# two_electrode_ECG.net
KiCad netlist of a schematic drawn in EAGLE
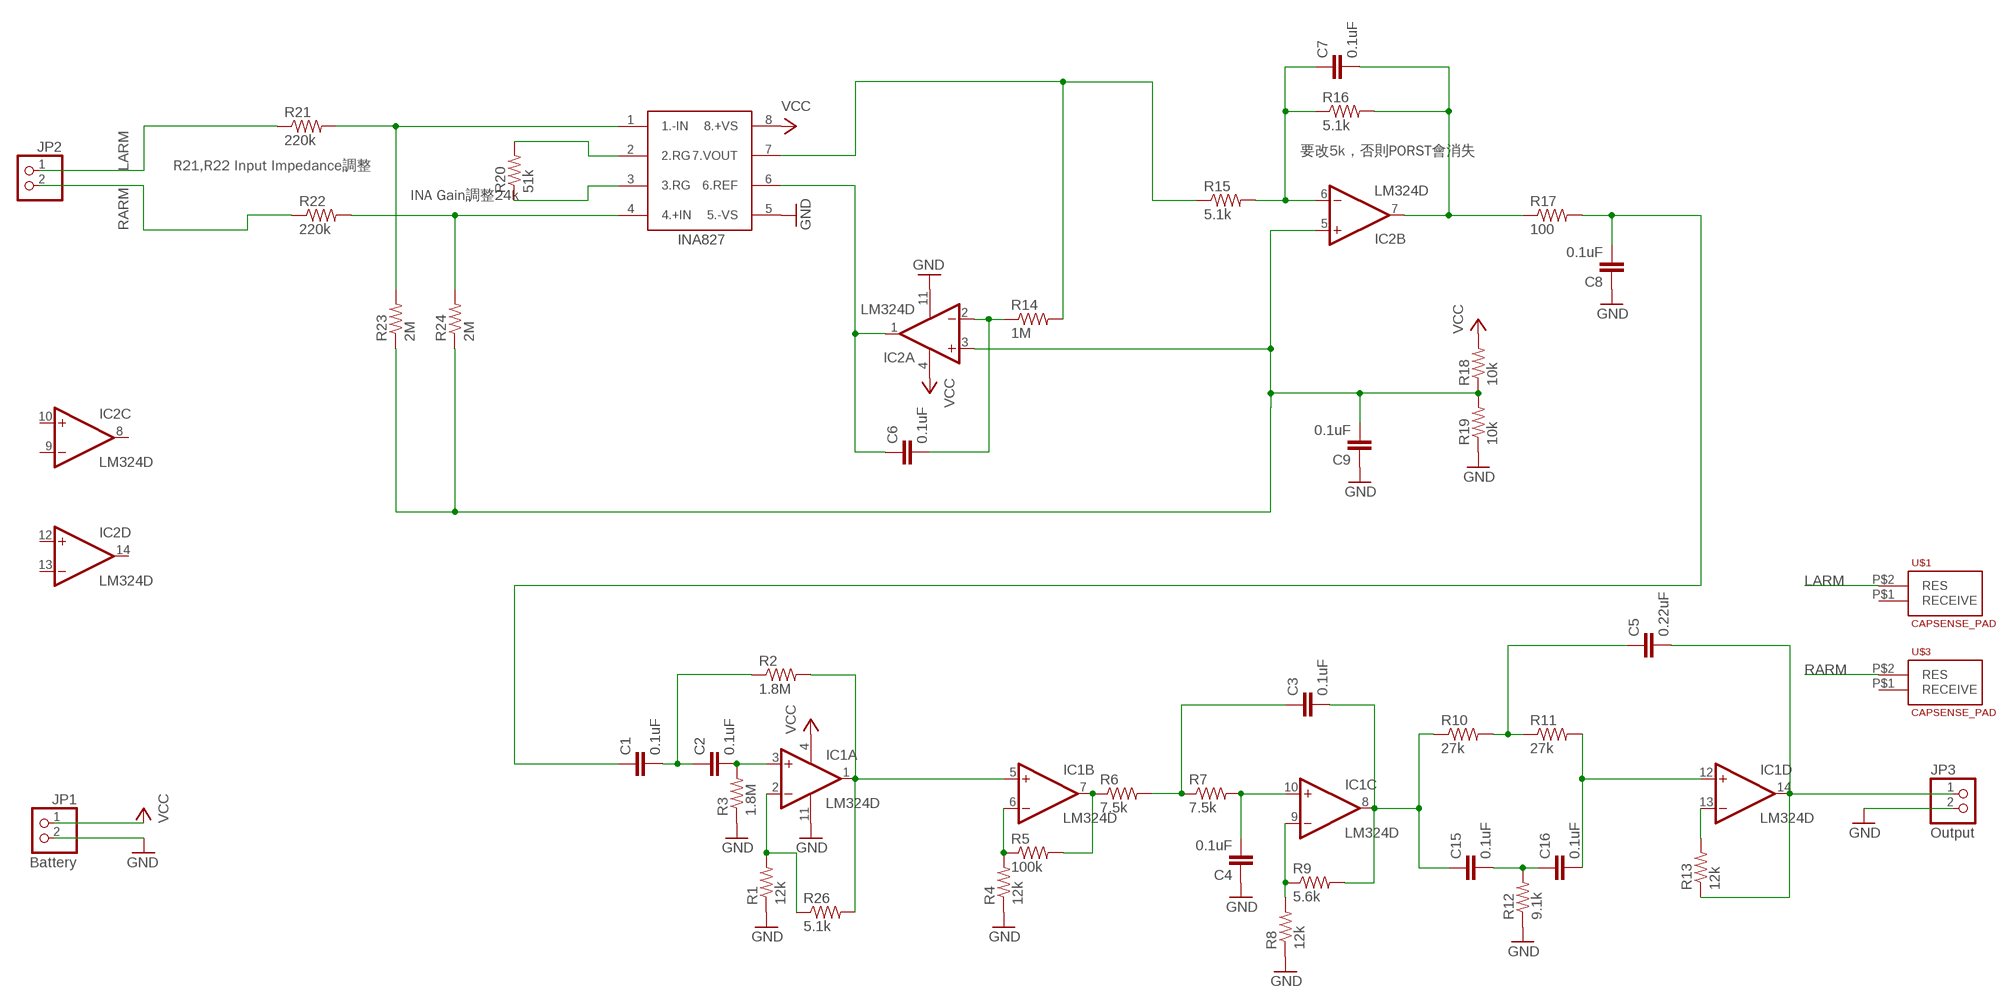
[diagram p0: schematic, sheet 1]

(export (version "E")
  (design (tool "Eeschema 10.0.6"))
  (components
    (comp (ref "C1")
      (value "0.1uF")
      (footprint "eagle-import:0603-CAP")
      (libsource (lib "eagle-import") (part "0.22UF-25V-10%(0603)"))
    )
    (comp (ref "C2")
      (value "0.1uF")
      (footprint "eagle-import:0603-CAP")
      (libsource (lib "eagle-import") (part "0.22UF-25V-10%(0603)"))
    )
    (comp (ref "C3")
      (value "0.1uF")
      (footprint "eagle-import:0603-CAP")
      (libsource (lib "eagle-import") (part "0.22UF-25V-10%(0603)"))
    )
    (comp (ref "C4")
      (value "0.1uF")
      (footprint "eagle-import:0603-CAP")
      (libsource (lib "eagle-import") (part "0.22UF-25V-10%(0603)"))
    )
    (comp (ref "C5")
      (value "0.22uF")
      (footprint "eagle-import:0603-CAP")
      (libsource (lib "eagle-import") (part "0.22UF-25V-10%(0603)"))
    )
    (comp (ref "C6")
      (value "0.1uF")
      (footprint "eagle-import:0603-CAP")
      (libsource (lib "eagle-import") (part "0.22UF-25V-10%(0603)"))
    )
    (comp (ref "C7")
      (value "0.1uF")
      (footprint "eagle-import:0603-CAP")
      (libsource (lib "eagle-import") (part "0.22UF-25V-10%(0603)"))
    )
    (comp (ref "C8")
      (value "0.1uF")
      (footprint "eagle-import:0603-CAP")
      (libsource (lib "eagle-import") (part "0.22UF-25V-10%(0603)"))
    )
    (comp (ref "C9")
      (value "0.1uF")
      (footprint "eagle-import:0603-CAP")
      (libsource (lib "eagle-import") (part "0.22UF-25V-10%(0603)"))
    )
    (comp (ref "C15")
      (value "0.1uF")
      (footprint "eagle-import:0603-CAP")
      (libsource (lib "eagle-import") (part "0.22UF-25V-10%(0603)"))
    )
    (comp (ref "C16")
      (value "0.1uF")
      (footprint "eagle-import:0603-CAP")
      (libsource (lib "eagle-import") (part "0.22UF-25V-10%(0603)"))
    )
    (comp (ref "IC1")
      (value "LM324D")
      (footprint "eagle-import:SO14")
      (libsource (lib "eagle-import") (part "LM324D"))
    )
    (comp (ref "IC2")
      (value "LM324D")
      (footprint "eagle-import:SO14")
      (libsource (lib "eagle-import") (part "LM324D"))
    )
    (comp (ref "JP1")
      (value "Battery")
      (footprint "eagle-import:1X02")
      (libsource (lib "eagle-import") (part "PINHD-1X2"))
    )
    (comp (ref "JP2")
      (value "PINHD-1X2")
      (footprint "eagle-import:1X02")
      (libsource (lib "eagle-import") (part "PINHD-1X2"))
    )
    (comp (ref "JP3")
      (value "Output")
      (footprint "eagle-import:1X02")
      (libsource (lib "eagle-import") (part "PINHD-1X2"))
    )
    (comp (ref "R1")
      (value "12k")
      (footprint "eagle-import:0603-RES")
      (libsource (lib "eagle-import") (part "1.2MOHMS-1/10W-1%(0603)"))
    )
    (comp (ref "R2")
      (value "1.8M")
      (footprint "eagle-import:0603-RES")
      (libsource (lib "eagle-import") (part "1.2MOHMS-1/10W-1%(0603)"))
    )
    (comp (ref "R3")
      (value "1.8M")
      (footprint "eagle-import:0603-RES")
      (libsource (lib "eagle-import") (part "1.2MOHMS-1/10W-1%(0603)"))
    )
    (comp (ref "R4")
      (value "12k")
      (footprint "eagle-import:0603-RES")
      (libsource (lib "eagle-import") (part "1.2MOHMS-1/10W-1%(0603)"))
    )
    (comp (ref "R5")
      (value "100k")
      (footprint "eagle-import:0603-RES")
      (libsource (lib "eagle-import") (part "1.2MOHMS-1/10W-1%(0603)"))
    )
    (comp (ref "R6")
      (value "7.5k")
      (footprint "eagle-import:0603-RES")
      (libsource (lib "eagle-import") (part "1.2MOHMS-1/10W-1%(0603)"))
    )
    (comp (ref "R7")
      (value "7.5k")
      (footprint "eagle-import:0603-RES")
      (libsource (lib "eagle-import") (part "1.2MOHMS-1/10W-1%(0603)"))
    )
    (comp (ref "R8")
      (value "12k")
      (footprint "eagle-import:0603-RES")
      (libsource (lib "eagle-import") (part "1.2MOHMS-1/10W-1%(0603)"))
    )
    (comp (ref "R9")
      (value "5.6k")
      (footprint "eagle-import:0603-RES")
      (libsource (lib "eagle-import") (part "1.2MOHMS-1/10W-1%(0603)"))
    )
    (comp (ref "R10")
      (value "27k")
      (footprint "eagle-import:0603-RES")
      (libsource (lib "eagle-import") (part "1.2MOHMS-1/10W-1%(0603)"))
    )
    (comp (ref "R11")
      (value "27k")
      (footprint "eagle-import:0603-RES")
      (libsource (lib "eagle-import") (part "1.2MOHMS-1/10W-1%(0603)"))
    )
    (comp (ref "R12")
      (value "9.1k")
      (footprint "eagle-import:0603-RES")
      (libsource (lib "eagle-import") (part "1.2MOHMS-1/10W-1%(0603)"))
    )
    (comp (ref "R13")
      (value "12k")
      (footprint "eagle-import:0603-RES")
      (libsource (lib "eagle-import") (part "1.2MOHMS-1/10W-1%(0603)"))
    )
    (comp (ref "R14")
      (value "1M")
      (footprint "eagle-import:0603-RES")
      (libsource (lib "eagle-import") (part "1.2MOHMS-1/10W-1%(0603)"))
    )
    (comp (ref "R15")
      (value "5.1k")
      (footprint "eagle-import:0603-RES")
      (libsource (lib "eagle-import") (part "1.2MOHMS-1/10W-1%(0603)"))
    )
    (comp (ref "R16")
      (value "5.1k")
      (footprint "eagle-import:0603-RES")
      (libsource (lib "eagle-import") (part "1.2MOHMS-1/10W-1%(0603)"))
    )
    (comp (ref "R17")
      (value "100")
      (footprint "eagle-import:0603-RES")
      (libsource (lib "eagle-import") (part "1.2MOHMS-1/10W-1%(0603)"))
    )
    (comp (ref "R18")
      (value "10k")
      (footprint "eagle-import:0603-RES")
      (libsource (lib "eagle-import") (part "1.2MOHMS-1/10W-1%(0603)"))
    )
    (comp (ref "R19")
      (value "10k")
      (footprint "eagle-import:0603-RES")
      (libsource (lib "eagle-import") (part "1.2MOHMS-1/10W-1%(0603)"))
    )
    (comp (ref "R20")
      (value "51k")
      (footprint "eagle-import:0603-RES")
      (libsource (lib "eagle-import") (part "1.2MOHMS-1/10W-1%(0603)"))
    )
    (comp (ref "R21")
      (value "220k")
      (footprint "eagle-import:0603-RES")
      (libsource (lib "eagle-import") (part "1.2MOHMS-1/10W-1%(0603)"))
    )
    (comp (ref "R22")
      (value "220k")
      (footprint "eagle-import:0603-RES")
      (libsource (lib "eagle-import") (part "1.2MOHMS-1/10W-1%(0603)"))
    )
    (comp (ref "R23")
      (value "2M")
      (footprint "eagle-import:0603-RES")
      (libsource (lib "eagle-import") (part "1.2MOHMS-1/10W-1%(0603)"))
    )
    (comp (ref "R24")
      (value "2M")
      (footprint "eagle-import:0603-RES")
      (libsource (lib "eagle-import") (part "1.2MOHMS-1/10W-1%(0603)"))
    )
    (comp (ref "R26")
      (value "5.1k")
      (footprint "eagle-import:0603-RES")
      (libsource (lib "eagle-import") (part "1.2MOHMS-1/10W-1%(0603)"))
    )
    (comp (ref "U$1")
      (value "CAPSENSE_PAD")
      (footprint "eagle-import:CAPSENSE_PAD")
      (libsource (lib "eagle-import") (part "CAPSENSE_PAD"))
    )
    (comp (ref "U$2")
      (value "INA827")
      (footprint "eagle-import:INA827")
      (libsource (lib "eagle-import") (part "INA827"))
    )
    (comp (ref "U$3")
      (value "CAPSENSE_PAD")
      (footprint "eagle-import:CAPSENSE_PAD")
      (libsource (lib "eagle-import") (part "CAPSENSE_PAD"))
    )
  )
  (nets
    (net (code "1") (name "/LARM") (class "Default")
      (node (ref "JP2") (pin "1") (pinfunction "1_1") (pintype "passive"))
      (node (ref "R21") (pin "1") (pinfunction "1_1") (pintype "passive"))
      (node (ref "U$1") (pin "P$2") (pinfunction "RES_P$2") (pintype "bidirectional"))
    )
    (net (code "2") (name "/RARM") (class "Default")
      (node (ref "JP2") (pin "2") (pinfunction "2_2") (pintype "passive"))
      (node (ref "R22") (pin "1") (pinfunction "1_1") (pintype "passive"))
      (node (ref "U$3") (pin "P$2") (pinfunction "RES_P$2") (pintype "bidirectional"))
    )
    (net (code "3") (name "GND") (class "Default")
      (node (ref "C4") (pin "1") (pinfunction "1_1") (pintype "passive"))
      (node (ref "C8") (pin "1") (pinfunction "1_1") (pintype "passive"))
      (node (ref "C9") (pin "1") (pinfunction "1_1") (pintype "passive"))
      (node (ref "IC1") (pin "11") (pinfunction "V-_11") (pintype "power_in"))
      (node (ref "IC2") (pin "11") (pinfunction "V-_11") (pintype "power_in"))
      (node (ref "JP1") (pin "2") (pinfunction "2_2") (pintype "passive"))
      (node (ref "JP3") (pin "2") (pinfunction "2_2") (pintype "passive"))
      (node (ref "R1") (pin "1") (pinfunction "1_1") (pintype "passive"))
      (node (ref "R12") (pin "1") (pinfunction "1_1") (pintype "passive"))
      (node (ref "R19") (pin "1") (pinfunction "1_1") (pintype "passive"))
      (node (ref "R3") (pin "1") (pinfunction "1_1") (pintype "passive"))
      (node (ref "R4") (pin "1") (pinfunction "1_1") (pintype "passive"))
      (node (ref "R8") (pin "1") (pinfunction "1_1") (pintype "passive"))
      (node (ref "U$2") (pin "5") (pinfunction "5.-VS_5") (pintype "bidirectional"))
    )
    (net (code "4") (name "Net-(C1-Pad1)") (class "Default")
      (node (ref "C1") (pin "1") (pinfunction "1_1") (pintype "passive"))
      (node (ref "C8") (pin "2") (pinfunction "2_2") (pintype "passive"))
      (node (ref "R17") (pin "2") (pinfunction "2_2") (pintype "passive"))
    )
    (net (code "5") (name "Net-(C1-Pad2)") (class "Default")
      (node (ref "C1") (pin "2") (pinfunction "2_2") (pintype "passive"))
      (node (ref "C2") (pin "1") (pinfunction "1_1") (pintype "passive"))
      (node (ref "R2") (pin "1") (pinfunction "1_1") (pintype "passive"))
    )
    (net (code "6") (name "Net-(C3-Pad1)") (class "Default")
      (node (ref "C3") (pin "1") (pinfunction "1_1") (pintype "passive"))
      (node (ref "R6") (pin "2") (pinfunction "2_2") (pintype "passive"))
      (node (ref "R7") (pin "1") (pinfunction "1_1") (pintype "passive"))
    )
    (net (code "7") (name "Net-(C5-Pad1)") (class "Default")
      (node (ref "C5") (pin "1") (pinfunction "1_1") (pintype "passive"))
      (node (ref "R10") (pin "2") (pinfunction "2_2") (pintype "passive"))
      (node (ref "R11") (pin "1") (pinfunction "1_1") (pintype "passive"))
    )
    (net (code "8") (name "Net-(C15-Pad2)") (class "Default")
      (node (ref "C15") (pin "2") (pinfunction "2_2") (pintype "passive"))
      (node (ref "C16") (pin "1") (pinfunction "1_1") (pintype "passive"))
      (node (ref "R12") (pin "2") (pinfunction "2_2") (pintype "passive"))
    )
    (net (code "9") (name "Net-(IC1A-+IN)") (class "Default")
      (node (ref "C2") (pin "2") (pinfunction "2_2") (pintype "passive"))
      (node (ref "IC1") (pin "3") (pinfunction "+IN_3") (pintype "input"))
      (node (ref "R3") (pin "2") (pinfunction "2_2") (pintype "passive"))
    )
    (net (code "10") (name "Net-(IC1A--IN)") (class "Default")
      (node (ref "IC1") (pin "2") (pinfunction "-IN_2") (pintype "input"))
      (node (ref "R1") (pin "2") (pinfunction "2_2") (pintype "passive"))
      (node (ref "R26") (pin "1") (pinfunction "1_1") (pintype "passive"))
    )
    (net (code "11") (name "Net-(IC1A-OUT)") (class "Default")
      (node (ref "IC1") (pin "1") (pinfunction "OUT_1") (pintype "output"))
      (node (ref "IC1") (pin "5") (pinfunction "+IN_5") (pintype "input"))
      (node (ref "R2") (pin "2") (pinfunction "2_2") (pintype "passive"))
      (node (ref "R26") (pin "2") (pinfunction "2_2") (pintype "passive"))
    )
    (net (code "12") (name "Net-(IC1B--IN)") (class "Default")
      (node (ref "IC1") (pin "6") (pinfunction "-IN_6") (pintype "input"))
      (node (ref "R4") (pin "2") (pinfunction "2_2") (pintype "passive"))
      (node (ref "R5") (pin "1") (pinfunction "1_1") (pintype "passive"))
    )
    (net (code "13") (name "Net-(IC1B-OUT)") (class "Default")
      (node (ref "IC1") (pin "7") (pinfunction "OUT_7") (pintype "output"))
      (node (ref "R5") (pin "2") (pinfunction "2_2") (pintype "passive"))
      (node (ref "R6") (pin "1") (pinfunction "1_1") (pintype "passive"))
    )
    (net (code "14") (name "Net-(IC1C-+IN)") (class "Default")
      (node (ref "C4") (pin "2") (pinfunction "2_2") (pintype "passive"))
      (node (ref "IC1") (pin "10") (pinfunction "+IN_10") (pintype "input"))
      (node (ref "R7") (pin "2") (pinfunction "2_2") (pintype "passive"))
    )
    (net (code "15") (name "Net-(IC1C--IN)") (class "Default")
      (node (ref "IC1") (pin "9") (pinfunction "-IN_9") (pintype "input"))
      (node (ref "R8") (pin "2") (pinfunction "2_2") (pintype "passive"))
      (node (ref "R9") (pin "1") (pinfunction "1_1") (pintype "passive"))
    )
    (net (code "16") (name "Net-(IC1C-OUT)") (class "Default")
      (node (ref "C15") (pin "1") (pinfunction "1_1") (pintype "passive"))
      (node (ref "C3") (pin "2") (pinfunction "2_2") (pintype "passive"))
      (node (ref "IC1") (pin "8") (pinfunction "OUT_8") (pintype "output"))
      (node (ref "R10") (pin "1") (pinfunction "1_1") (pintype "passive"))
      (node (ref "R9") (pin "2") (pinfunction "2_2") (pintype "passive"))
    )
    (net (code "17") (name "Net-(IC1D-+IN)") (class "Default")
      (node (ref "C16") (pin "2") (pinfunction "2_2") (pintype "passive"))
      (node (ref "IC1") (pin "12") (pinfunction "+IN_12") (pintype "input"))
      (node (ref "R11") (pin "2") (pinfunction "2_2") (pintype "passive"))
    )
    (net (code "18") (name "Net-(IC1D--IN)") (class "Default")
      (node (ref "IC1") (pin "13") (pinfunction "-IN_13") (pintype "input"))
      (node (ref "R13") (pin "2") (pinfunction "2_2") (pintype "passive"))
    )
    (net (code "19") (name "Net-(IC1D-OUT)") (class "Default")
      (node (ref "C5") (pin "2") (pinfunction "2_2") (pintype "passive"))
      (node (ref "IC1") (pin "14") (pinfunction "OUT_14") (pintype "output"))
      (node (ref "JP3") (pin "1") (pinfunction "1_1") (pintype "passive"))
      (node (ref "R13") (pin "1") (pinfunction "1_1") (pintype "passive"))
    )
    (net (code "20") (name "Net-(IC2A-+IN)") (class "Default")
      (node (ref "C9") (pin "2") (pinfunction "2_2") (pintype "passive"))
      (node (ref "IC2") (pin "3") (pinfunction "+IN_3") (pintype "input"))
      (node (ref "IC2") (pin "5") (pinfunction "+IN_5") (pintype "input"))
      (node (ref "R18") (pin "1") (pinfunction "1_1") (pintype "passive"))
      (node (ref "R19") (pin "2") (pinfunction "2_2") (pintype "passive"))
      (node (ref "R23") (pin "1") (pinfunction "1_1") (pintype "passive"))
      (node (ref "R24") (pin "1") (pinfunction "1_1") (pintype "passive"))
    )
    (net (code "21") (name "Net-(IC2A--IN)") (class "Default")
      (node (ref "C6") (pin "2") (pinfunction "2_2") (pintype "passive"))
      (node (ref "IC2") (pin "2") (pinfunction "-IN_2") (pintype "input"))
      (node (ref "R14") (pin "1") (pinfunction "1_1") (pintype "passive"))
    )
    (net (code "22") (name "Net-(IC2A-OUT)") (class "Default")
      (node (ref "C6") (pin "1") (pinfunction "1_1") (pintype "passive"))
      (node (ref "IC2") (pin "1") (pinfunction "OUT_1") (pintype "output"))
      (node (ref "U$2") (pin "6") (pinfunction "6.REF_6") (pintype "bidirectional"))
    )
    (net (code "23") (name "Net-(IC2B--IN)") (class "Default")
      (node (ref "C7") (pin "1") (pinfunction "1_1") (pintype "passive"))
      (node (ref "IC2") (pin "6") (pinfunction "-IN_6") (pintype "input"))
      (node (ref "R15") (pin "2") (pinfunction "2_2") (pintype "passive"))
      (node (ref "R16") (pin "1") (pinfunction "1_1") (pintype "passive"))
    )
    (net (code "24") (name "Net-(IC2B-OUT)") (class "Default")
      (node (ref "C7") (pin "2") (pinfunction "2_2") (pintype "passive"))
      (node (ref "IC2") (pin "7") (pinfunction "OUT_7") (pintype "output"))
      (node (ref "R16") (pin "2") (pinfunction "2_2") (pintype "passive"))
      (node (ref "R17") (pin "1") (pinfunction "1_1") (pintype "passive"))
    )
    (net (code "25") (name "Net-(U$2-1.-IN)") (class "Default")
      (node (ref "R21") (pin "2") (pinfunction "2_2") (pintype "passive"))
      (node (ref "R23") (pin "2") (pinfunction "2_2") (pintype "passive"))
      (node (ref "U$2") (pin "1") (pinfunction "1.-IN_1") (pintype "bidirectional"))
    )
    (net (code "26") (name "Net-(U$2-2.RG)") (class "Default")
      (node (ref "R20") (pin "2") (pinfunction "2_2") (pintype "passive"))
      (node (ref "U$2") (pin "2") (pinfunction "2.RG_2") (pintype "bidirectional"))
    )
    (net (code "27") (name "Net-(U$2-3.RG)") (class "Default")
      (node (ref "R20") (pin "1") (pinfunction "1_1") (pintype "passive"))
      (node (ref "U$2") (pin "3") (pinfunction "3.RG_3") (pintype "bidirectional"))
    )
    (net (code "28") (name "Net-(U$2-4.+IN)") (class "Default")
      (node (ref "R22") (pin "2") (pinfunction "2_2") (pintype "passive"))
      (node (ref "R24") (pin "2") (pinfunction "2_2") (pintype "passive"))
      (node (ref "U$2") (pin "4") (pinfunction "4.+IN_4") (pintype "bidirectional"))
    )
    (net (code "29") (name "Net-(U$2-7.VOUT)") (class "Default")
      (node (ref "R14") (pin "2") (pinfunction "2_2") (pintype "passive"))
      (node (ref "R15") (pin "1") (pinfunction "1_1") (pintype "passive"))
      (node (ref "U$2") (pin "7") (pinfunction "7.VOUT_7") (pintype "bidirectional"))
    )
    (net (code "30") (name "VCC") (class "Default")
      (node (ref "IC1") (pin "4") (pinfunction "V+_4") (pintype "power_in"))
      (node (ref "IC2") (pin "4") (pinfunction "V+_4") (pintype "power_in"))
      (node (ref "JP1") (pin "1") (pinfunction "1_1") (pintype "passive"))
      (node (ref "R18") (pin "2") (pinfunction "2_2") (pintype "passive"))
      (node (ref "U$2") (pin "8") (pinfunction "8.+VS_8") (pintype "bidirectional"))
    )
    (net (code "31") (name "unconnected-(IC2C-+IN-Pad10)") (class "Default")
      (node (ref "IC2") (pin "10") (pinfunction "+IN_10") (pintype "input"))
    )
    (net (code "32") (name "unconnected-(IC2C--IN-Pad9)") (class "Default")
      (node (ref "IC2") (pin "9") (pinfunction "-IN_9") (pintype "input"))
    )
    (net (code "33") (name "unconnected-(IC2C-OUT-Pad8)") (class "Default")
      (node (ref "IC2") (pin "8") (pinfunction "OUT_8") (pintype "output"))
    )
    (net (code "34") (name "unconnected-(IC2D-+IN-Pad12)") (class "Default")
      (node (ref "IC2") (pin "12") (pinfunction "+IN_12") (pintype "input"))
    )
    (net (code "35") (name "unconnected-(IC2D--IN-Pad13)") (class "Default")
      (node (ref "IC2") (pin "13") (pinfunction "-IN_13") (pintype "input"))
    )
    (net (code "36") (name "unconnected-(IC2D-OUT-Pad14)") (class "Default")
      (node (ref "IC2") (pin "14") (pinfunction "OUT_14") (pintype "output"))
    )
    (net (code "37") (name "unconnected-(U$1-RECEIVE-PadP$1)") (class "Default")
      (node (ref "U$1") (pin "P$1") (pinfunction "RECEIVE_P$1") (pintype "bidirectional"))
    )
    (net (code "38") (name "unconnected-(U$3-RECEIVE-PadP$1)") (class "Default")
      (node (ref "U$3") (pin "P$1") (pinfunction "RECEIVE_P$1") (pintype "bidirectional"))
    )
  )
)
